# MachXO2FPGA.net
KiCad netlist of a schematic drawn in Altium Designer
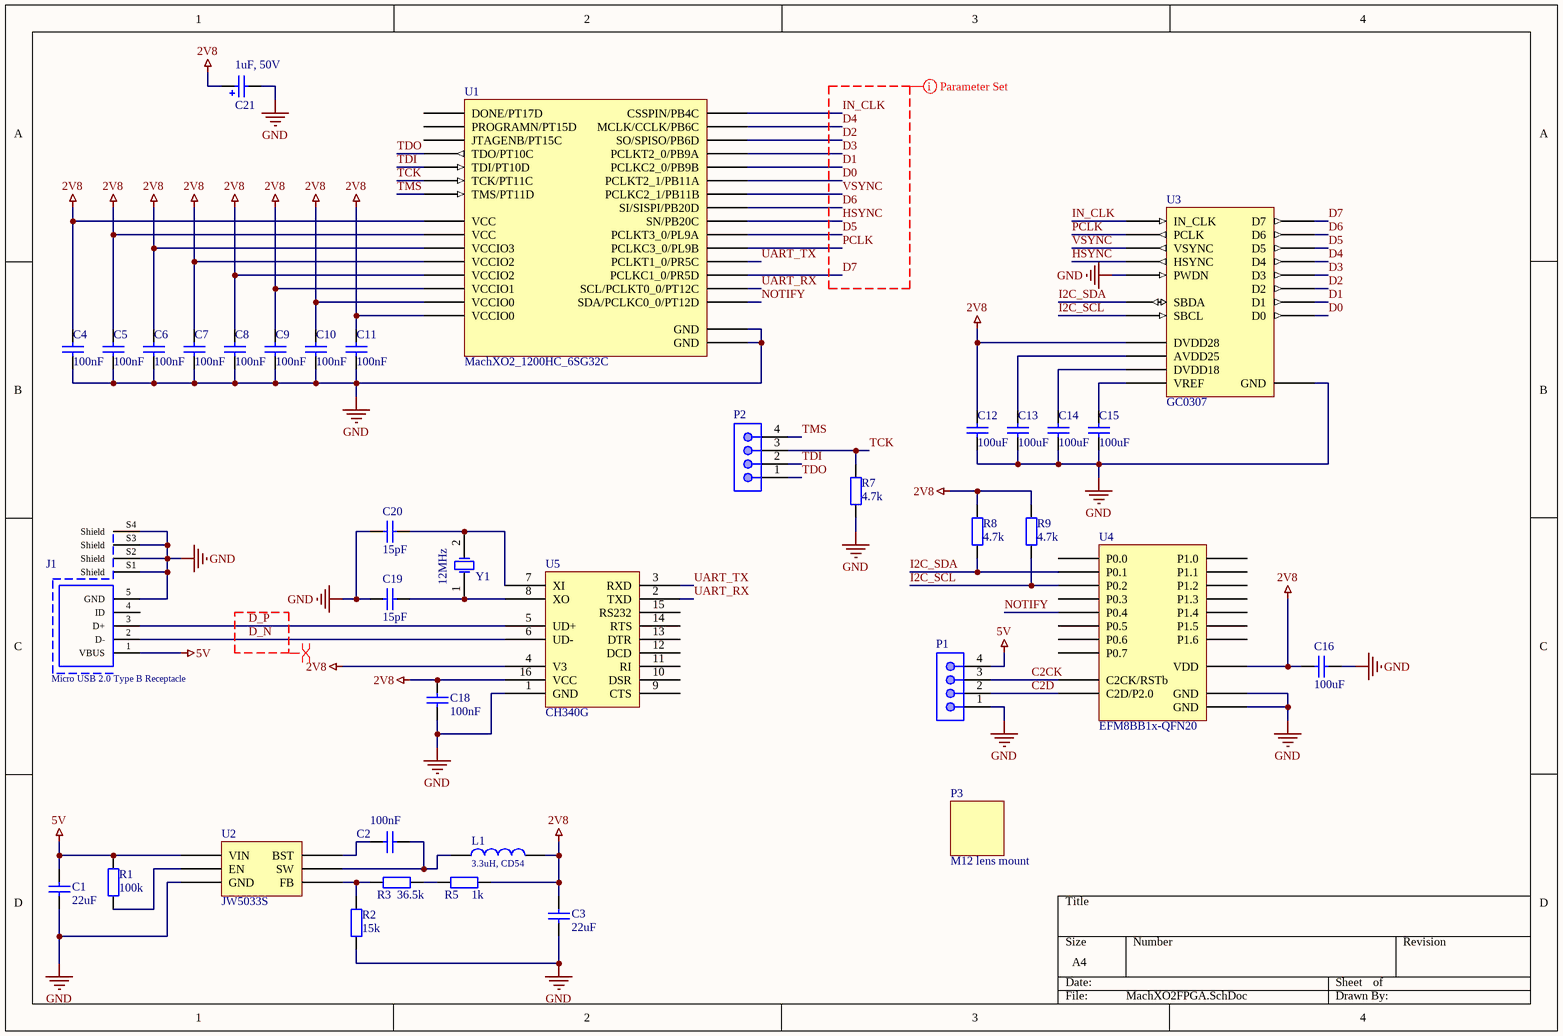
[diagram p0: MachXO2FPGA.SchDoc]

(export (version "E")
  (design (tool "Eeschema 10.0.6"))
  (components
    (comp (ref "C1")
      (value "22uF")
      (footprint "WCAP-CSGP_0805_H=0.8mm_Reflow")
      (description "WCAP-CSGP General Purpose Ceramic Capacitors, size 0805, 100nF, +/-10%, 10VDC")
      (fields (field (name "PART NUMBER") "885012207016") (field (name "PUBLISHER") "Wurth Elektronik"))
      (libsource (lib "Altium_WCAP-CSGP (rev19a)") (part "885012207016"))
    )
    (comp (ref "C2")
      (value "100nF")
      (footprint "WCAP-CSGP_0805_H=0.8mm_Reflow")
      (description "WCAP-CSGP General Purpose Ceramic Capacitors, size 0805, 100nF, +/-10%, 10VDC")
      (fields (field (name "PART NUMBER") "885012207016") (field (name "PUBLISHER") "Wurth Elektronik"))
      (libsource (lib "Altium_WCAP-CSGP (rev19a)") (part "885012207016"))
    )
    (comp (ref "C3")
      (value "22uF")
      (footprint "WCAP-CSGP_0805_H=0.8mm_Reflow")
      (description "WCAP-CSGP General Purpose Ceramic Capacitors, size 0805, 100nF, +/-10%, 10VDC")
      (fields (field (name "PART NUMBER") "885012207016") (field (name "PUBLISHER") "Wurth Elektronik"))
      (libsource (lib "Altium_WCAP-CSGP (rev19a)") (part "885012207016"))
    )
    (comp (ref "C4")
      (value "100nF")
      (footprint "WCAP-CSGP_0805_H=0.8mm_Reflow")
      (description "WCAP-CSGP General Purpose Ceramic Capacitors, size 0805, 100nF, +/-10%, 10VDC")
      (fields (field (name "PART NUMBER") "885012207016") (field (name "PUBLISHER") "Wurth Elektronik"))
      (libsource (lib "Altium_WCAP-CSGP (rev19a)") (part "885012207016"))
    )
    (comp (ref "C5")
      (value "100nF")
      (footprint "WCAP-CSGP_0805_H=0.8mm_Reflow")
      (description "WCAP-CSGP General Purpose Ceramic Capacitors, size 0805, 100nF, +/-10%, 10VDC")
      (fields (field (name "PART NUMBER") "885012207016") (field (name "PUBLISHER") "Wurth Elektronik"))
      (libsource (lib "Altium_WCAP-CSGP (rev19a)") (part "885012207016"))
    )
    (comp (ref "C6")
      (value "100nF")
      (footprint "WCAP-CSGP_0805_H=0.8mm_Reflow")
      (description "WCAP-CSGP General Purpose Ceramic Capacitors, size 0805, 100nF, +/-10%, 10VDC")
      (fields (field (name "PART NUMBER") "885012207016") (field (name "PUBLISHER") "Wurth Elektronik"))
      (libsource (lib "Altium_WCAP-CSGP (rev19a)") (part "885012207016"))
    )
    (comp (ref "C7")
      (value "100nF")
      (footprint "WCAP-CSGP_0805_H=0.8mm_Reflow")
      (description "WCAP-CSGP General Purpose Ceramic Capacitors, size 0805, 100nF, +/-10%, 10VDC")
      (fields (field (name "PART NUMBER") "885012207016") (field (name "PUBLISHER") "Wurth Elektronik"))
      (libsource (lib "Altium_WCAP-CSGP (rev19a)") (part "885012207016"))
    )
    (comp (ref "C8")
      (value "100nF")
      (footprint "WCAP-CSGP_0805_H=0.8mm_Reflow")
      (description "WCAP-CSGP General Purpose Ceramic Capacitors, size 0805, 100nF, +/-10%, 10VDC")
      (fields (field (name "PART NUMBER") "885012207016") (field (name "PUBLISHER") "Wurth Elektronik"))
      (libsource (lib "Altium_WCAP-CSGP (rev19a)") (part "885012207016"))
    )
    (comp (ref "C9")
      (value "100nF")
      (footprint "WCAP-CSGP_0805_H=0.8mm_Reflow")
      (description "WCAP-CSGP General Purpose Ceramic Capacitors, size 0805, 100nF, +/-10%, 10VDC")
      (fields (field (name "PART NUMBER") "885012207016") (field (name "PUBLISHER") "Wurth Elektronik"))
      (libsource (lib "Altium_WCAP-CSGP (rev19a)") (part "885012207016"))
    )
    (comp (ref "C10")
      (value "100nF")
      (footprint "WCAP-CSGP_0805_H=0.8mm_Reflow")
      (description "WCAP-CSGP General Purpose Ceramic Capacitors, size 0805, 100nF, +/-10%, 10VDC")
      (fields (field (name "PART NUMBER") "885012207016") (field (name "PUBLISHER") "Wurth Elektronik"))
      (libsource (lib "Altium_WCAP-CSGP (rev19a)") (part "885012207016"))
    )
    (comp (ref "C11")
      (value "100nF")
      (footprint "WCAP-CSGP_0805_H=0.8mm_Reflow")
      (description "WCAP-CSGP General Purpose Ceramic Capacitors, size 0805, 100nF, +/-10%, 10VDC")
      (fields (field (name "PART NUMBER") "885012207016") (field (name "PUBLISHER") "Wurth Elektronik"))
      (libsource (lib "Altium_WCAP-CSGP (rev19a)") (part "885012207016"))
    )
    (comp (ref "C12")
      (value "100uF")
      (footprint "WCAP-CSGP_0805_H=0.8mm_Reflow")
      (description "WCAP-CSGP General Purpose Ceramic Capacitors, size 0805, 100nF, +/-10%, 10VDC")
      (fields (field (name "PART NUMBER") "885012207016") (field (name "PUBLISHER") "Wurth Elektronik"))
      (libsource (lib "Altium_WCAP-CSGP (rev19a)") (part "885012207016"))
    )
    (comp (ref "C13")
      (value "100uF")
      (footprint "WCAP-CSGP_0805_H=0.8mm_Reflow")
      (description "WCAP-CSGP General Purpose Ceramic Capacitors, size 0805, 100nF, +/-10%, 10VDC")
      (fields (field (name "PART NUMBER") "885012207016") (field (name "PUBLISHER") "Wurth Elektronik"))
      (libsource (lib "Altium_WCAP-CSGP (rev19a)") (part "885012207016"))
    )
    (comp (ref "C14")
      (value "100uF")
      (footprint "WCAP-CSGP_0805_H=0.8mm_Reflow")
      (description "WCAP-CSGP General Purpose Ceramic Capacitors, size 0805, 100nF, +/-10%, 10VDC")
      (fields (field (name "PART NUMBER") "885012207016") (field (name "PUBLISHER") "Wurth Elektronik"))
      (libsource (lib "Altium_WCAP-CSGP (rev19a)") (part "885012207016"))
    )
    (comp (ref "C15")
      (value "100uF")
      (footprint "WCAP-CSGP_0805_H=0.8mm_Reflow")
      (description "WCAP-CSGP General Purpose Ceramic Capacitors, size 0805, 100nF, +/-10%, 10VDC")
      (fields (field (name "PART NUMBER") "885012207016") (field (name "PUBLISHER") "Wurth Elektronik"))
      (libsource (lib "Altium_WCAP-CSGP (rev19a)") (part "885012207016"))
    )
    (comp (ref "C16")
      (value "100uF")
      (footprint "WCAP-CSGP_0805_H=0.8mm_Reflow")
      (description "WCAP-CSGP General Purpose Ceramic Capacitors, size 0805, 100nF, +/-10%, 10VDC")
      (fields (field (name "PART NUMBER") "885012207016") (field (name "PUBLISHER") "Wurth Elektronik"))
      (libsource (lib "Altium_WCAP-CSGP (rev19a)") (part "885012207016"))
    )
    (comp (ref "C18")
      (value "100nF")
      (footprint "WCAP-CSGP_0805_H=0.8mm_Reflow")
      (description "WCAP-CSGP General Purpose Ceramic Capacitors, size 0805, 100nF, +/-10%, 10VDC")
      (fields (field (name "PART NUMBER") "885012207016") (field (name "PUBLISHER") "Wurth Elektronik"))
      (libsource (lib "Altium_WCAP-CSGP (rev19a)") (part "885012207016"))
    )
    (comp (ref "C19")
      (value "15pF")
      (footprint "WCAP-CSGP_0805_H=0.6mm_Reflow")
      (description "WCAP-CSGP General Purpose Ceramic Capacitors, size 0805, 15pF, +/-5%, 10VDC")
      (fields (field (name "PART NUMBER") "885012007001") (field (name "PUBLISHER") "Wurth Elektronik"))
      (libsource (lib "Altium_WCAP-CSGP (rev19a)") (part "885012007001"))
    )
    (comp (ref "C20")
      (value "15pF")
      (footprint "WCAP-CSGP_0805_H=0.6mm_Reflow")
      (description "WCAP-CSGP General Purpose Ceramic Capacitors, size 0805, 15pF, +/-5%, 10VDC")
      (fields (field (name "PART NUMBER") "885012007001") (field (name "PUBLISHER") "Wurth Elektronik"))
      (libsource (lib "Altium_WCAP-CSGP (rev19a)") (part "885012007001"))
    )
    (comp (ref "C21")
      (value "1uF, 50V")
      (footprint "WCAP-ATG8_5x11")
      (description "WCAP-ATG8 THT Aluminum Electrolytic Capacitors, D5mm x L11mm, 1uF, +/-20%, 50VDC")
      (fields (field (name "PART NUMBER") "860010672005") (field (name "PUBLISHER") "Wurth Elektronik"))
      (libsource (lib "Altium_WCAP-ATG8_rev19a") (part "860010672005"))
    )
    (comp (ref "J1")
      (value "Micro USB 2.0 Type B Receptacle")
      (footprint "629105136821")
      (description "Micro USB 2.0 Type B, Receptacle, Horizontal, SMT")
      (fields (field (name "PART NUMBER") "629105136821") (field (name "PUBLISHER") "Wurth Elektronik"))
      (libsource (lib "Altium_WR-COM_USB-Connectors (rev19b)") (part "629105136821"))
    )
    (comp (ref "L1")
      (value "3.3uH, CD54")
      (footprint "WE-PD2_5848")
      (description "WE-PD2 SMT Power Inductor, size 5848, 2.2uH, 4.6A")
      (fields
        (field (name "MANUFACTURER") "Wurth Elektronik")
        (field (name "MANUFACTURER PART NUMBER") "744774022")
      )
      (libsource (lib "744774022_Altium_WE-PD2_rev20a") (part "744774022"))
    )
    (comp (ref "P1")
      (value "~")
      (footprint "61300411021")
      (description "WR-PHD Pin Header, THT, pitch 2.54mm, Single Row, Angled, 4p")
      (fields
        (field (name "MANUFACTURER PART NUMBER") "61300411021")
        (field (name "MANUFACTURER") "Wurth Elektronik")
      )
      (libsource (lib "61300311021_Altium_WR-PHD_rev20a") (part "61300411021"))
    )
    (comp (ref "P2")
      (value "~")
      (footprint "61300411021")
      (description "WR-PHD Pin Header, THT, pitch 2.54mm, Single Row, Angled, 4p")
      (fields
        (field (name "MANUFACTURER PART NUMBER") "61300411021")
        (field (name "MANUFACTURER") "Wurth Elektronik")
      )
      (libsource (lib "61300311021_Altium_WR-PHD_rev20a") (part "61300411021"))
    )
    (comp (ref "P3")
      (value "M12 lens mount")
      (footprint "PCBComponent_1")
      (libsource (lib "M12_Lens_Mount") (part "M12 lens mount"))
    )
    (comp (ref "R1")
      (value "100k")
      (footprint "WRIS-PSMB_0805_H=0.22mm")
      (description "WRIS-PSMB Metal Plate Resistors, size 0805, 10mOhm, +/-1%, 0.5W")
      (fields (field (name "PART NUMBER") "580060720008") (field (name "PUBLISHER") "Wurth Elektronik"))
      (libsource (lib "Altium_WRIS-PSMB (rev19a)") (part "580060720008"))
    )
    (comp (ref "R2")
      (value "15k")
      (footprint "WRIS-PSMB_0805_H=0.22mm")
      (description "WRIS-PSMB Metal Plate Resistors, size 0805, 10mOhm, +/-1%, 0.5W")
      (fields (field (name "PART NUMBER") "580060720008") (field (name "PUBLISHER") "Wurth Elektronik"))
      (libsource (lib "Altium_WRIS-PSMB (rev19a)") (part "580060720008"))
    )
    (comp (ref "R3")
      (value "36.5k")
      (footprint "WRIS-PSMB_0805_H=0.22mm")
      (description "WRIS-PSMB Metal Plate Resistors, size 0805, 10mOhm, +/-1%, 0.5W")
      (fields (field (name "PART NUMBER") "580060720008") (field (name "PUBLISHER") "Wurth Elektronik"))
      (libsource (lib "") (part "580060720008_1"))
    )
    (comp (ref "R5")
      (value "1k")
      (footprint "WRIS-PSMB_0805_H=0.22mm")
      (description "WRIS-PSMB Metal Plate Resistors, size 0805, 10mOhm, +/-1%, 0.5W")
      (fields (field (name "PART NUMBER") "580060720008") (field (name "PUBLISHER") "Wurth Elektronik"))
      (libsource (lib "") (part "580060720008_1"))
    )
    (comp (ref "R7")
      (value "4.7k")
      (footprint "WRIS-PSMB_0805_H=0.22mm")
      (description "WRIS-PSMB Metal Plate Resistors, size 0805, 10mOhm, +/-1%, 0.5W")
      (fields (field (name "PART NUMBER") "580060720008") (field (name "PUBLISHER") "Wurth Elektronik"))
      (libsource (lib "Altium_WRIS-PSMB (rev19a)") (part "580060720008"))
    )
    (comp (ref "R8")
      (value "4.7k")
      (footprint "WRIS-PSMB_0805_H=0.22mm")
      (description "WRIS-PSMB Metal Plate Resistors, size 0805, 10mOhm, +/-1%, 0.5W")
      (fields (field (name "PART NUMBER") "580060720008") (field (name "PUBLISHER") "Wurth Elektronik"))
      (libsource (lib "Altium_WRIS-PSMB (rev19a)") (part "580060720008"))
    )
    (comp (ref "R9")
      (value "4.7k")
      (footprint "WRIS-PSMB_0805_H=0.22mm")
      (description "WRIS-PSMB Metal Plate Resistors, size 0805, 10mOhm, +/-1%, 0.5W")
      (fields (field (name "PART NUMBER") "580060720008") (field (name "PUBLISHER") "Wurth Elektronik"))
      (libsource (lib "Altium_WRIS-PSMB (rev19a)") (part "580060720008"))
    )
    (comp (ref "U1")
      (value "MachXO2_1200HC_6SG32C")
      (footprint "QFN50P500X500X65_HS-33N")
      (libsource (lib "MachXO2_1200HC_6SG32C") (part "MachXO2_1200HC_6SG32C"))
    )
    (comp (ref "U2")
      (value "JW5033S")
      (footprint "SOT95P280X110-6N")
      (description "2A Step-Down Converter")
      (libsource (lib "JW5033S") (part "JW5033S"))
    )
    (comp (ref "U3")
      (value "GC0307")
      (footprint "BGA20C60P5X4_329X276X78")
      (libsource (lib "GC0307") (part "GC0307"))
    )
    (comp (ref "U4")
      (value "EFM8BB1x-QFN20")
      (footprint "*QFN50P300X300X80-21N")
      (libsource (lib "EFM8BB1x_QFN20") (part "EFM8BB1x-QFN20"))
    )
    (comp (ref "U5") (value "CH340G") (footprint "CH340G") (libsource (lib "CH340G") (part "CH340G")))
    (comp (ref "Y1")
      (value "12MHz")
      (footprint "WE-XTAL_HC49/4H")
      (description "WE-XTAL Quartz Crystal, size HC49 12MHz")
      (fields (field (name "PART NUMBER") "830014948B") (field (name "PUBLISHER") "Wurth Elektronik"))
      (libsource (lib "Altium_WE-XTAL (rev19a)") (part "830014948B"))
    )
  )
  (nets
    (net (code "1") (name "/C2CK") (class "Default")
      (node (ref "P1") (pin "3") (pinfunction "3_3") (pintype "passive"))
      (node (ref "U4") (pin "5") (pinfunction "C2CK/RSTb_5") (pintype "passive"))
    )
    (net (code "2") (name "/C2D") (class "Default")
      (node (ref "P1") (pin "2") (pinfunction "2_2") (pintype "passive"))
      (node (ref "U4") (pin "6") (pinfunction "C2D/P2.0_6") (pintype "passive"))
    )
    (net (code "3") (name "/D0") (class "Default")
      (node (ref "U1") (pin "13") (pinfunction "PCLKT2_1/PB11A_13") (pintype "passive"))
      (node (ref "U3") (pin "C2") (pinfunction "D0_C2") (pintype "output"))
    )
    (net (code "4") (name "/D1") (class "Default")
      (node (ref "U1") (pin "12") (pinfunction "PCLKC2_0/PB9B_12") (pintype "passive"))
      (node (ref "U3") (pin "D2") (pinfunction "D1_D2") (pintype "output"))
    )
    (net (code "5") (name "/D2") (class "Default")
      (node (ref "U1") (pin "10") (pinfunction "SO/SPISO/PB6D_10") (pintype "passive"))
      (node (ref "U3") (pin "D3") (pinfunction "D2_D3") (pintype "output"))
    )
    (net (code "6") (name "/D3") (class "Default")
      (node (ref "U1") (pin "11") (pinfunction "PCLKT2_0/PB9A_11") (pintype "passive"))
      (node (ref "U3") (pin "C3") (pinfunction "D3_C3") (pintype "output"))
    )
    (net (code "7") (name "/D4") (class "Default")
      (node (ref "U1") (pin "9") (pinfunction "MCLK/CCLK/PB6C_9") (pintype "passive"))
      (node (ref "U3") (pin "C4") (pinfunction "D4_C4") (pintype "output"))
    )
    (net (code "8") (name "/D5") (class "Default")
      (node (ref "U1") (pin "4") (pinfunction "PCLKT3_0/PL9A_4") (pintype "passive"))
      (node (ref "U3") (pin "B5") (pinfunction "D5_B5") (pintype "output"))
    )
    (net (code "9") (name "/D6") (class "Default")
      (node (ref "U1") (pin "17") (pinfunction "SI/SISPI/PB20D_17") (pintype "passive"))
      (node (ref "U3") (pin "B4") (pinfunction "D6_B4") (pintype "output"))
    )
    (net (code "10") (name "/D7") (class "Default")
      (node (ref "U1") (pin "20") (pinfunction "PCLKC1_0/PR5D_20") (pintype "passive"))
      (node (ref "U3") (pin "A5") (pinfunction "D7_A5") (pintype "output"))
    )
    (net (code "11") (name "/D_N") (class "Default")
      (node (ref "J1") (pin "2") (pinfunction "D-_2") (pintype "passive"))
      (node (ref "U5") (pin "6") (pinfunction "UD-_6") (pintype "passive"))
    )
    (net (code "12") (name "/D_P") (class "Default")
      (node (ref "J1") (pin "3") (pinfunction "D+_3") (pintype "passive"))
      (node (ref "U5") (pin "5") (pinfunction "UD+_5") (pintype "passive"))
    )
    (net (code "13") (name "/HSYNC") (class "Default")
      (node (ref "U1") (pin "16") (pinfunction "SN/PB20C_16") (pintype "passive"))
      (node (ref "U3") (pin "B3") (pinfunction "HSYNC_B3") (pintype "output"))
    )
    (net (code "14") (name "/I2C_SCL") (class "Default")
      (node (ref "R9") (pin "1") (pinfunction "1_1") (pintype "passive"))
      (node (ref "U3") (pin "A4") (pinfunction "SBCL_A4") (pintype "input"))
      (node (ref "U4") (pin "20") (pinfunction "P0.2_20") (pintype "passive"))
    )
    (net (code "15") (name "/I2C_SDA") (class "Default")
      (node (ref "R8") (pin "1") (pinfunction "1_1") (pintype "passive"))
      (node (ref "U3") (pin "A3") (pinfunction "SBDA_A3") (pintype "bidirectional"))
      (node (ref "U4") (pin "1") (pinfunction "P0.1_1") (pintype "passive"))
    )
    (net (code "16") (name "/IN_CLK") (class "Default")
      (node (ref "U1") (pin "8") (pinfunction "CSSPIN/PB4C_8") (pintype "passive"))
      (node (ref "U3") (pin "D5") (pinfunction "IN_CLK_D5") (pintype "input"))
    )
    (net (code "17") (name "/NOTIFY") (class "Default")
      (node (ref "U1") (pin "27") (pinfunction "SDA/PCLKC0_0/PT12D_27") (pintype "passive"))
      (node (ref "U4") (pin "18") (pinfunction "P0.4_18") (pintype "passive"))
    )
    (net (code "18") (name "/PCLK") (class "Default")
      (node (ref "U1") (pin "5") (pinfunction "PCLKC3_0/PL9B_5") (pintype "passive"))
      (node (ref "U3") (pin "C5") (pinfunction "PCLK_C5") (pintype "output"))
    )
    (net (code "19") (name "/TCK") (class "Default")
      (node (ref "P2") (pin "3") (pinfunction "3_3") (pintype "passive"))
      (node (ref "R7") (pin "2") (pinfunction "2_2") (pintype "passive"))
      (node (ref "U1") (pin "30") (pinfunction "TCK/PT11C_30") (pintype "input"))
    )
    (net (code "20") (name "/TDI") (class "Default")
      (node (ref "P2") (pin "2") (pinfunction "2_2") (pintype "passive"))
      (node (ref "U1") (pin "32") (pinfunction "TDI/PT10D_32") (pintype "input"))
    )
    (net (code "21") (name "/TDO") (class "Default")
      (node (ref "P2") (pin "1") (pinfunction "1_1") (pintype "passive"))
      (node (ref "U1") (pin "1") (pinfunction "TDO/PT10C_1") (pintype "output"))
    )
    (net (code "22") (name "/TMS") (class "Default")
      (node (ref "P2") (pin "4") (pinfunction "4_4") (pintype "passive"))
      (node (ref "U1") (pin "29") (pinfunction "TMS/PT11D_29") (pintype "input"))
    )
    (net (code "23") (name "/UART_RX") (class "Default")
      (node (ref "U1") (pin "28") (pinfunction "SCL/PCLKT0_0/PT12C_28") (pintype "passive"))
      (node (ref "U5") (pin "2") (pinfunction "TXD_2") (pintype "passive"))
    )
    (net (code "24") (name "/UART_TX") (class "Default")
      (node (ref "U1") (pin "21") (pinfunction "PCLKT1_0/PR5C_21") (pintype "passive"))
      (node (ref "U5") (pin "3") (pinfunction "RXD_3") (pintype "passive"))
    )
    (net (code "25") (name "/VSYNC") (class "Default")
      (node (ref "U1") (pin "14") (pinfunction "PCLKC2_1/PB11B_14") (pintype "passive"))
      (node (ref "U3") (pin "C1") (pinfunction "VSYNC_C1") (pintype "output"))
    )
    (net (code "26") (name "2V8") (class "Default")
      (node (ref "C10") (pin "1") (pinfunction "1_1") (pintype "passive"))
      (node (ref "C11") (pin "1") (pinfunction "1_1") (pintype "passive"))
      (node (ref "C12") (pin "1") (pinfunction "1_1") (pintype "passive"))
      (node (ref "C16") (pin "1") (pinfunction "1_1") (pintype "passive"))
      (node (ref "C18") (pin "2") (pinfunction "2_2") (pintype "passive"))
      (node (ref "C21") (pin "2") (pinfunction "P_2") (pintype "passive"))
      (node (ref "C3") (pin "1") (pinfunction "1_1") (pintype "passive"))
      (node (ref "C4") (pin "1") (pinfunction "1_1") (pintype "passive"))
      (node (ref "C5") (pin "1") (pinfunction "1_1") (pintype "passive"))
      (node (ref "C6") (pin "1") (pinfunction "1_1") (pintype "passive"))
      (node (ref "C7") (pin "1") (pinfunction "1_1") (pintype "passive"))
      (node (ref "C8") (pin "1") (pinfunction "1_1") (pintype "passive"))
      (node (ref "C9") (pin "1") (pinfunction "1_1") (pintype "passive"))
      (node (ref "L1") (pin "2") (pinfunction "2_2") (pintype "passive"))
      (node (ref "R5") (pin "2") (pinfunction "2_2") (pintype "passive"))
      (node (ref "R8") (pin "2") (pinfunction "2_2") (pintype "passive"))
      (node (ref "R9") (pin "2") (pinfunction "2_2") (pintype "passive"))
      (node (ref "U1") (pin "15") (pinfunction "VCCIO2_15") (pintype "passive"))
      (node (ref "U1") (pin "18") (pinfunction "VCC_18") (pintype "passive"))
      (node (ref "U1") (pin "19") (pinfunction "VCCIO1_19") (pintype "passive"))
      (node (ref "U1") (pin "2") (pinfunction "VCC_2") (pintype "passive"))
      (node (ref "U1") (pin "24") (pinfunction "VCCIO0_24") (pintype "passive"))
      (node (ref "U1") (pin "31") (pinfunction "VCCIO0_31") (pintype "passive"))
      (node (ref "U1") (pin "6") (pinfunction "VCCIO3_6") (pintype "passive"))
      (node (ref "U1") (pin "7") (pinfunction "VCCIO2_7") (pintype "passive"))
      (node (ref "U3") (pin "D1") (pinfunction "DVDD28_D1") (pintype "passive"))
      (node (ref "U4") (pin "4") (pinfunction "VDD_4") (pintype "passive"))
      (node (ref "U5") (pin "16") (pinfunction "VCC_16") (pintype "passive"))
      (node (ref "U5") (pin "4") (pinfunction "V3_4") (pintype "passive"))
    )
    (net (code "27") (name "5V") (class "Default")
      (node (ref "C1") (pin "2") (pinfunction "2_2") (pintype "passive"))
      (node (ref "J1") (pin "1") (pinfunction "VBUS_1") (pintype "passive"))
      (node (ref "P1") (pin "4") (pinfunction "4_4") (pintype "passive"))
      (node (ref "R1") (pin "2") (pinfunction "2_2") (pintype "passive"))
      (node (ref "U2") (pin "3") (pinfunction "VIN_3") (pintype "passive"))
    )
    (net (code "28") (name "GND") (class "Default")
      (node (ref "C1") (pin "1") (pinfunction "1_1") (pintype "passive"))
      (node (ref "C10") (pin "2") (pinfunction "2_2") (pintype "passive"))
      (node (ref "C11") (pin "2") (pinfunction "2_2") (pintype "passive"))
      (node (ref "C12") (pin "2") (pinfunction "2_2") (pintype "passive"))
      (node (ref "C13") (pin "2") (pinfunction "2_2") (pintype "passive"))
      (node (ref "C14") (pin "2") (pinfunction "2_2") (pintype "passive"))
      (node (ref "C15") (pin "2") (pinfunction "2_2") (pintype "passive"))
      (node (ref "C16") (pin "2") (pinfunction "2_2") (pintype "passive"))
      (node (ref "C18") (pin "1") (pinfunction "1_1") (pintype "passive"))
      (node (ref "C19") (pin "1") (pinfunction "1_1") (pintype "passive"))
      (node (ref "C20") (pin "2") (pinfunction "2_2") (pintype "passive"))
      (node (ref "C21") (pin "1") (pinfunction "N_1") (pintype "passive"))
      (node (ref "C3") (pin "2") (pinfunction "2_2") (pintype "passive"))
      (node (ref "C4") (pin "2") (pinfunction "2_2") (pintype "passive"))
      (node (ref "C5") (pin "2") (pinfunction "2_2") (pintype "passive"))
      (node (ref "C6") (pin "2") (pinfunction "2_2") (pintype "passive"))
      (node (ref "C7") (pin "2") (pinfunction "2_2") (pintype "passive"))
      (node (ref "C8") (pin "2") (pinfunction "2_2") (pintype "passive"))
      (node (ref "C9") (pin "2") (pinfunction "2_2") (pintype "passive"))
      (node (ref "J1") (pin "5") (pinfunction "GND_5") (pintype "passive"))
      (node (ref "J1") (pin "S1") (pinfunction "Shield_S1") (pintype "passive"))
      (node (ref "J1") (pin "S2") (pinfunction "Shield_S2") (pintype "passive"))
      (node (ref "J1") (pin "S3") (pinfunction "Shield_S3") (pintype "passive"))
      (node (ref "J1") (pin "S4") (pinfunction "Shield_S4") (pintype "passive"))
      (node (ref "P1") (pin "1") (pinfunction "1_1") (pintype "passive"))
      (node (ref "R2") (pin "1") (pinfunction "1_1") (pintype "passive"))
      (node (ref "R7") (pin "1") (pinfunction "1_1") (pintype "passive"))
      (node (ref "U1") (pin "22") (pinfunction "GND_22") (pintype "passive"))
      (node (ref "U1") (pin "3") (pinfunction "GND_3") (pintype "passive"))
      (node (ref "U2") (pin "1") (pinfunction "GND_1") (pintype "passive"))
      (node (ref "U3") (pin "B1") (pinfunction "GND_B1") (pintype "power_in"))
      (node (ref "U3") (pin "B2") (pinfunction "PWDN_B2") (pintype "input"))
      (node (ref "U4") (pin "12") (pinfunction "GND_12") (pintype "passive"))
      (node (ref "U4") (pin "3") (pinfunction "GND_3") (pintype "passive"))
      (node (ref "U5") (pin "1") (pinfunction "GND_1") (pintype "passive"))
    )
    (net (code "29") (name "Net-(R3-Pad2)") (class "Default")
      (node (ref "R3") (pin "2") (pinfunction "2_2") (pintype "passive"))
      (node (ref "R5") (pin "1") (pinfunction "1_1") (pintype "passive"))
    )
    (net (code "30") (name "Net-(U2-BST)") (class "Default")
      (node (ref "C2") (pin "2") (pinfunction "2_2") (pintype "passive"))
      (node (ref "U2") (pin "4") (pinfunction "BST_4") (pintype "passive"))
    )
    (net (code "31") (name "Net-(U2-EN)") (class "Default")
      (node (ref "R1") (pin "1") (pinfunction "1_1") (pintype "passive"))
      (node (ref "U2") (pin "5") (pinfunction "EN_5") (pintype "passive"))
    )
    (net (code "32") (name "Net-(U2-FB)") (class "Default")
      (node (ref "R2") (pin "2") (pinfunction "2_2") (pintype "passive"))
      (node (ref "R3") (pin "1") (pinfunction "1_1") (pintype "passive"))
      (node (ref "U2") (pin "6") (pinfunction "FB_6") (pintype "passive"))
    )
    (net (code "33") (name "Net-(U2-SW)") (class "Default")
      (node (ref "C2") (pin "1") (pinfunction "1_1") (pintype "passive"))
      (node (ref "L1") (pin "1") (pinfunction "1_1") (pintype "passive"))
      (node (ref "U2") (pin "2") (pinfunction "SW_2") (pintype "passive"))
    )
    (net (code "34") (name "Net-(U3-AVDD25)") (class "Default")
      (node (ref "C13") (pin "1") (pinfunction "1_1") (pintype "passive"))
      (node (ref "U3") (pin "A1") (pinfunction "AVDD25_A1") (pintype "power_in"))
    )
    (net (code "35") (name "Net-(U3-DVDD18)") (class "Default")
      (node (ref "C14") (pin "1") (pinfunction "1_1") (pintype "passive"))
      (node (ref "U3") (pin "D4") (pinfunction "DVDD18_D4") (pintype "passive"))
    )
    (net (code "36") (name "Net-(U3-VREF)") (class "Default")
      (node (ref "C15") (pin "1") (pinfunction "1_1") (pintype "passive"))
      (node (ref "U3") (pin "A2") (pinfunction "VREF_A2") (pintype "power_in"))
    )
    (net (code "37") (name "Net-(U5-XI)") (class "Default")
      (node (ref "C20") (pin "1") (pinfunction "1_1") (pintype "passive"))
      (node (ref "U5") (pin "7") (pinfunction "XI_7") (pintype "passive"))
      (node (ref "Y1") (pin "2") (pinfunction "OSC2_2") (pintype "passive"))
    )
    (net (code "38") (name "Net-(U5-XO)") (class "Default")
      (node (ref "C19") (pin "2") (pinfunction "2_2") (pintype "passive"))
      (node (ref "U5") (pin "8") (pinfunction "XO_8") (pintype "passive"))
      (node (ref "Y1") (pin "1") (pinfunction "OSC1_1") (pintype "passive"))
    )
    (net (code "39") (name "unconnected-(J1-ID-Pad4)") (class "Default")
      (node (ref "J1") (pin "4") (pinfunction "ID_4") (pintype "passive"))
    )
    (net (code "40") (name "unconnected-(U1-DONE{slash}PT17D-Pad23)") (class "Default")
      (node (ref "U1") (pin "23") (pinfunction "DONE/PT17D_23") (pintype "passive"))
    )
    (net (code "41") (name "unconnected-(U1-JTAGENB{slash}PT15C-Pad26)") (class "Default")
      (node (ref "U1") (pin "26") (pinfunction "JTAGENB/PT15C_26") (pintype "passive"))
    )
    (net (code "42") (name "unconnected-(U1-PROGRAMN{slash}PT15D-Pad25)") (class "Default")
      (node (ref "U1") (pin "25") (pinfunction "PROGRAMN/PT15D_25") (pintype "passive"))
    )
    (net (code "43") (name "unconnected-(U4-P0.0-Pad2)") (class "Default")
      (node (ref "U4") (pin "2") (pinfunction "P0.0_2") (pintype "passive"))
    )
    (net (code "44") (name "unconnected-(U4-P0.3-Pad19)") (class "Default")
      (node (ref "U4") (pin "19") (pinfunction "P0.3_19") (pintype "passive"))
    )
    (net (code "45") (name "unconnected-(U4-P0.5-Pad17)") (class "Default")
      (node (ref "U4") (pin "17") (pinfunction "P0.5_17") (pintype "passive"))
    )
    (net (code "46") (name "unconnected-(U4-P0.6-Pad16)") (class "Default")
      (node (ref "U4") (pin "16") (pinfunction "P0.6_16") (pintype "passive"))
    )
    (net (code "47") (name "unconnected-(U4-P0.7-Pad15)") (class "Default")
      (node (ref "U4") (pin "15") (pinfunction "P0.7_15") (pintype "passive"))
    )
    (net (code "48") (name "unconnected-(U4-P1.0-Pad14)") (class "Default")
      (node (ref "U4") (pin "14") (pinfunction "P1.0_14") (pintype "passive"))
    )
    (net (code "49") (name "unconnected-(U4-P1.1-Pad13)") (class "Default")
      (node (ref "U4") (pin "13") (pinfunction "P1.1_13") (pintype "passive"))
    )
    (net (code "50") (name "unconnected-(U4-P1.2-Pad11)") (class "Default")
      (node (ref "U4") (pin "11") (pinfunction "P1.2_11") (pintype "passive"))
    )
    (net (code "51") (name "unconnected-(U4-P1.3-Pad10)") (class "Default")
      (node (ref "U4") (pin "10") (pinfunction "P1.3_10") (pintype "passive"))
    )
    (net (code "52") (name "unconnected-(U4-P1.4-Pad9)") (class "Default")
      (node (ref "U4") (pin "9") (pinfunction "P1.4_9") (pintype "passive"))
    )
    (net (code "53") (name "unconnected-(U4-P1.5-Pad8)") (class "Default")
      (node (ref "U4") (pin "8") (pinfunction "P1.5_8") (pintype "passive"))
    )
    (net (code "54") (name "unconnected-(U4-P1.6-Pad7)") (class "Default")
      (node (ref "U4") (pin "7") (pinfunction "P1.6_7") (pintype "passive"))
    )
    (net (code "55") (name "unconnected-(U5-CTS-Pad9)") (class "Default")
      (node (ref "U5") (pin "9") (pinfunction "CTS_9") (pintype "passive"))
    )
    (net (code "56") (name "unconnected-(U5-DCD-Pad12)") (class "Default")
      (node (ref "U5") (pin "12") (pinfunction "DCD_12") (pintype "passive"))
    )
    (net (code "57") (name "unconnected-(U5-DSR-Pad10)") (class "Default")
      (node (ref "U5") (pin "10") (pinfunction "DSR_10") (pintype "passive"))
    )
    (net (code "58") (name "unconnected-(U5-DTR-Pad13)") (class "Default")
      (node (ref "U5") (pin "13") (pinfunction "DTR_13") (pintype "passive"))
    )
    (net (code "59") (name "unconnected-(U5-RI-Pad11)") (class "Default")
      (node (ref "U5") (pin "11") (pinfunction "RI_11") (pintype "passive"))
    )
    (net (code "60") (name "unconnected-(U5-RS232-Pad15)") (class "Default")
      (node (ref "U5") (pin "15") (pinfunction "RS232_15") (pintype "passive"))
    )
    (net (code "61") (name "unconnected-(U5-RTS-Pad14)") (class "Default")
      (node (ref "U5") (pin "14") (pinfunction "RTS_14") (pintype "passive"))
    )
  )
)
